# Microocontroller.net
KiCad netlist of a schematic drawn in Altium Designer
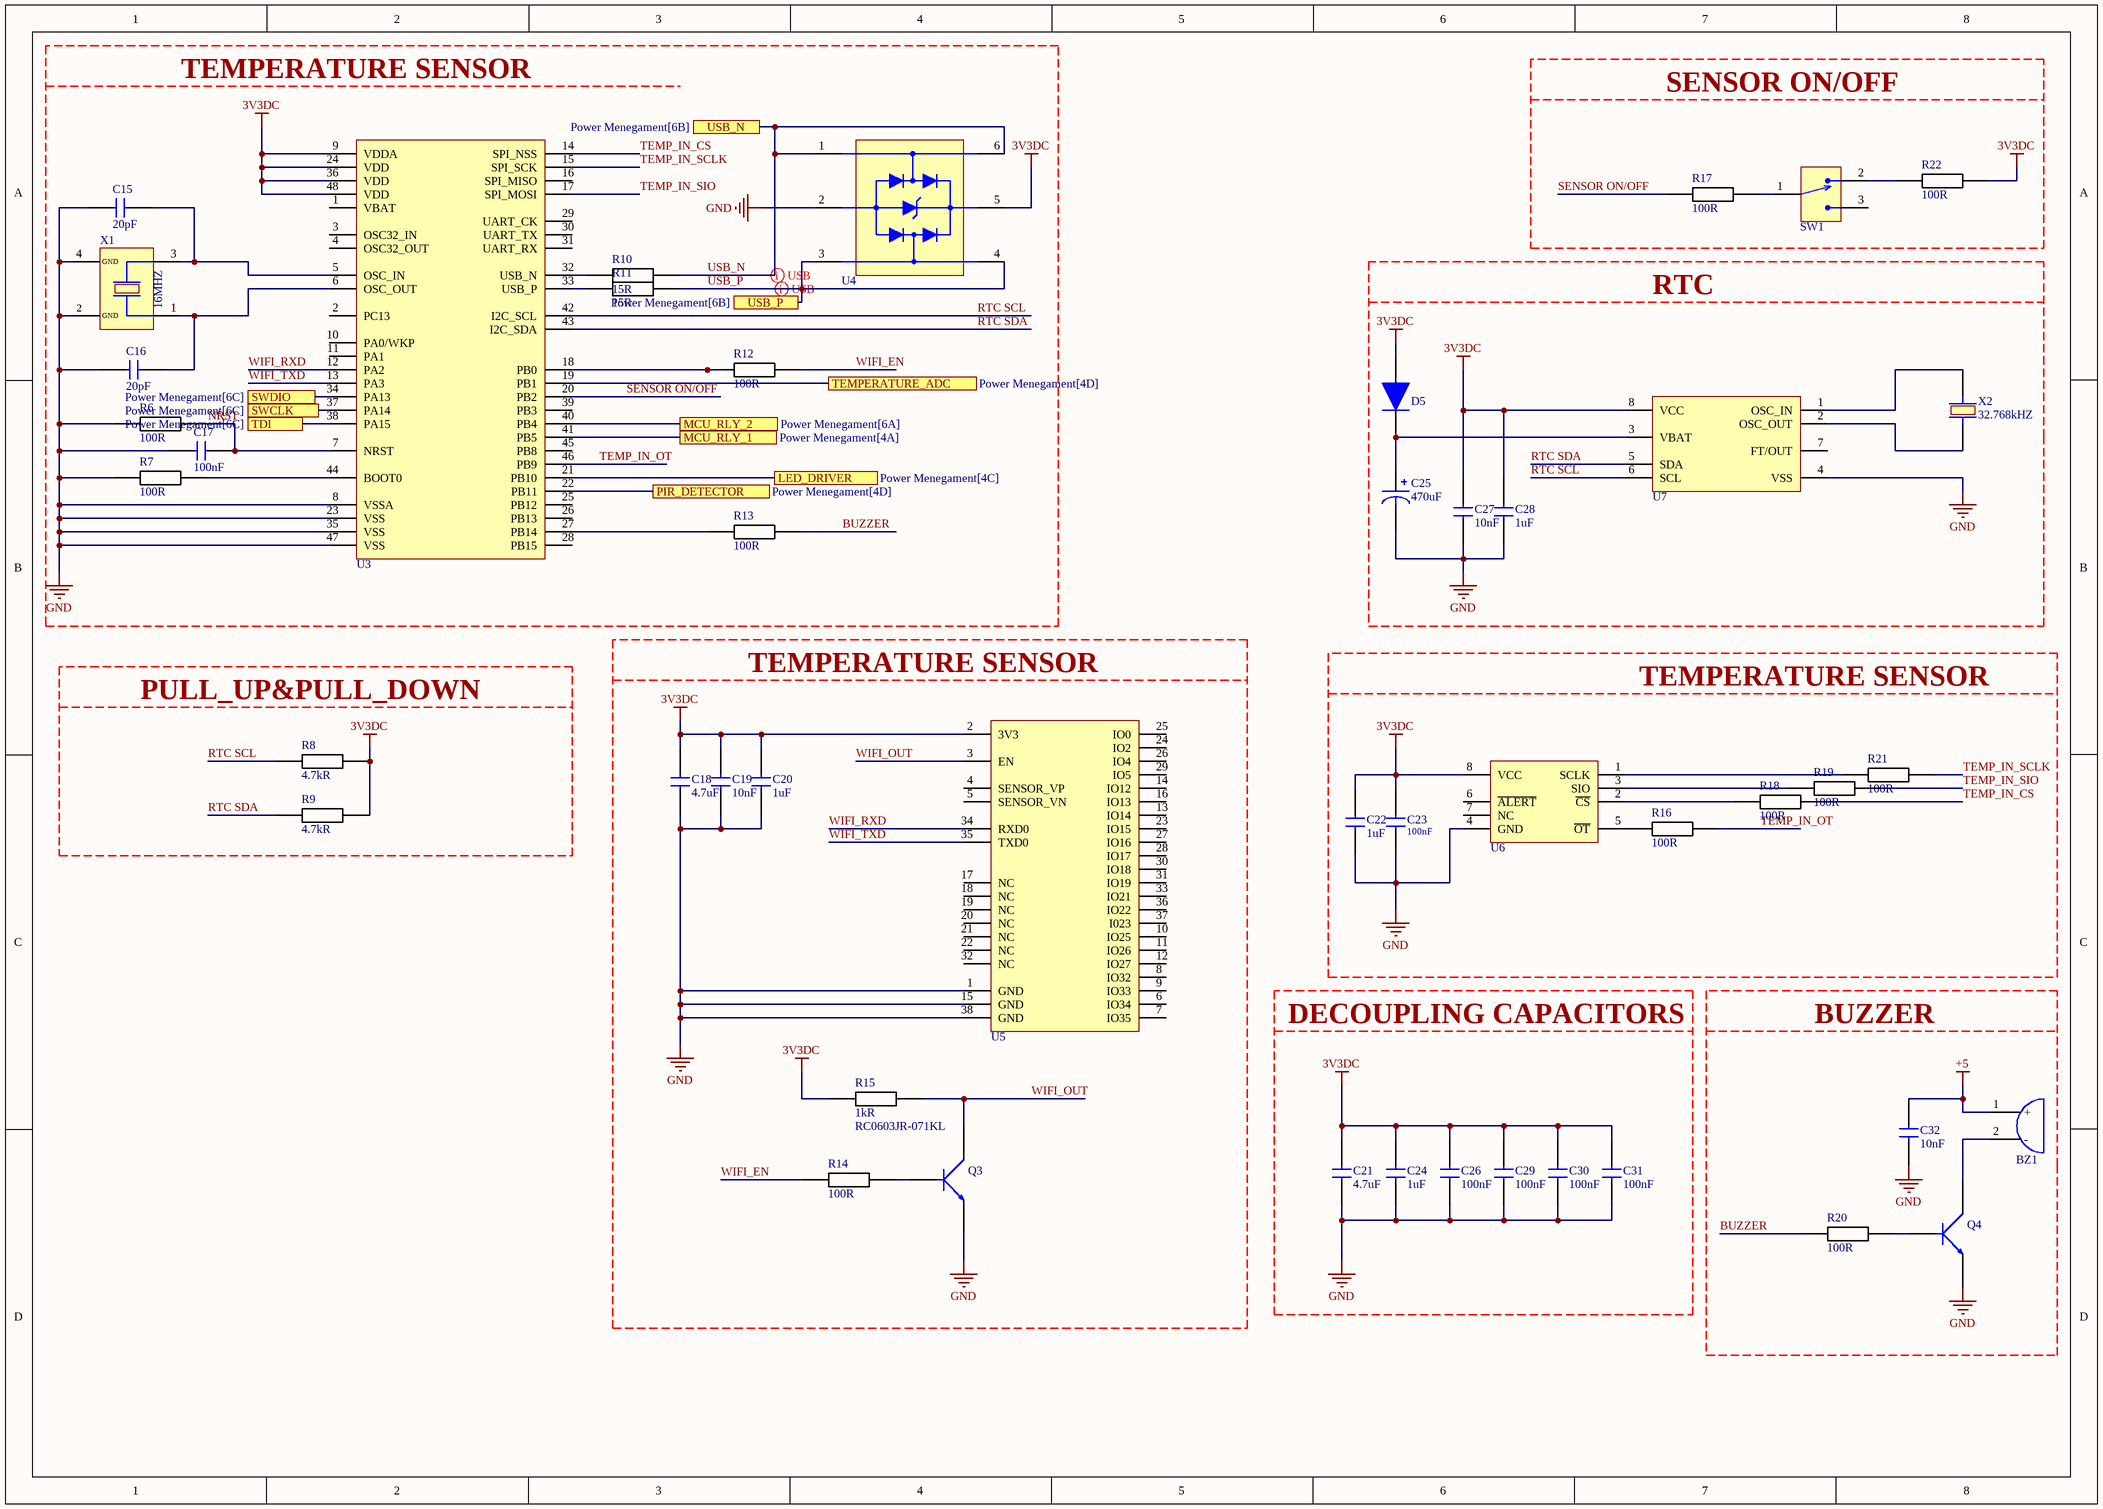
[diagram p0: Microocontroller.SchDoc]

(export (version "E")
  (design (tool "Eeschema 10.0.6"))
  (components
    (comp (ref "BZ1")
      (value "CMI-9605IC-0580T")
      (footprint "CMI-9605IC")
      (description "Buzzers Indicator, Internally Driven Magnetic 5 V 30mA 2.7kHz 80dB @ 5V, 10cm Through Hole PC Pins")
      (fields (field (name "MANUFACTURER") "CUI Devices") (field (name "DESIGNED BY") "Kerem"))
      (libsource (lib "library") (part "CMI-9605IC-0580T"))
    )
    (comp (ref "C15")
      (value "20pF")
      (footprint "CAP_0603")
      (description "Ceramic Capacitor, 50V, 0.00002uF, Surface Mount, 0603")
      (fields
        (field (name "MANUFACTURER") "Samsung")
        (field (name "MANUFACTURER PART NUMBER") "CL10C200JB8NNNC")
        (field (name "DESIGNED BY") "Kerem")
      )
      (libsource (lib "library") (part "CAP_CER_20pF_0603"))
    )
    (comp (ref "C16")
      (value "20pF")
      (footprint "CAP_0603")
      (description "Ceramic Capacitor, 50V, 0.00002uF, Surface Mount, 0603")
      (fields
        (field (name "MANUFACTURER") "Samsung")
        (field (name "MANUFACTURER PART NUMBER") "CL10C200JB8NNNC")
        (field (name "DESIGNED BY") "Kerem")
      )
      (libsource (lib "library") (part "CAP_CER_20pF_0603"))
    )
    (comp (ref "C17")
      (value "100nF")
      (footprint "CAP_0805")
      (description "Ceramic Capacitor,50V, %10, 0.1uF, Surface Mount, 0805")
      (fields
        (field (name "MANUFACTURER") "Samsung")
        (field (name "MANUFACTURER PART NUMBER") "CL21B104KBCNNNC")
        (field (name "DESIGNED BY") "Kerem")
      )
      (libsource (lib "library") (part "CAP_CER_100nF_0805"))
    )
    (comp (ref "C18")
      (value "4.7uF")
      (footprint "CAP_0805")
      (description "CAP CER 4.7uF,%10, Surface Mount, 0805")
      (fields
        (field (name "MANUFACTURER") "Samsung")
        (field (name "MANUFACTURER PART NUMBER") "CL21A475KAQNNNE")
        (field (name "DESIGNED BY") "Kerem")
      )
      (libsource (lib "library") (part "CAP_CER_4.7uF_0805"))
    )
    (comp (ref "C19")
      (value "10nF")
      (footprint "CAP_0603")
      (description "Ceramic Capacitor,16V, 10%, 0.01uF, Surface Mount, 0603")
      (fields
        (field (name "MANUFACTURER") "Walsin Technologies")
        (field (name "MANUFACTURER PART NUMBER") "0603B103K160CT")
        (field (name "DESIGNED BY") "Kerem")
      )
      (libsource (lib "library") (part "CAP_CER_10nF_0603"))
    )
    (comp (ref "C20")
      (value "1uF")
      (footprint "CAP_0805")
      (description "Cap CER, 1uF, 16V, 0805;")
      (fields
        (field (name "MANUFACTURER") "KEMET")
        (field (name "MANUFACTURER PART NUMBER") "CHA08C105K4RXL7189")
        (field (name "DESIGNED BY") "Kerem")
      )
      (libsource (lib "library") (part "CAP_CER_1uF_0805"))
    )
    (comp (ref "C21")
      (value "4.7uF")
      (footprint "CAP_0805")
      (description "CAP CER 4.7uF,%10, Surface Mount, 0805")
      (fields
        (field (name "MANUFACTURER") "Samsung")
        (field (name "MANUFACTURER PART NUMBER") "CL21A475KAQNNNE")
        (field (name "DESIGNED BY") "Kerem")
      )
      (libsource (lib "library") (part "CAP_CER_4.7uF_0805"))
    )
    (comp (ref "C22")
      (value "1uF")
      (footprint "CAP_0805")
      (description "Cap CER, 1uF, 16V, 0805;")
      (fields
        (field (name "MANUFACTURER") "KEMET")
        (field (name "MANUFACTURER PART NUMBER") "CHA08C105K4RXL7189")
        (field (name "DESIGNED BY") "Kerem")
      )
      (libsource (lib "library") (part "CAP_CER_1uF_0805"))
    )
    (comp (ref "C23")
      (value "100nF")
      (footprint "CAP_0603")
      (description "0.1 µF ±20% 50V Ceramic Capacitor X7R 0603 (1608 Metric)")
      (fields
        (field (name "MANUFACTURER") "KEMET")
        (field (name "MANUFACTURER PART NUMBER") "C0603C104M5RACTU")
      )
      (libsource (lib "library") (part "CAP CER 100nF 0603"))
    )
    (comp (ref "C24")
      (value "1uF")
      (footprint "CAP_0805")
      (description "Cap CER, 1uF, 16V, 0805;")
      (fields
        (field (name "MANUFACTURER") "KEMET")
        (field (name "MANUFACTURER PART NUMBER") "CHA08C105K4RXL7189")
        (field (name "DESIGNED BY") "Kerem")
      )
      (libsource (lib "library") (part "CAP_CER_1uF_0805"))
    )
    (comp (ref "C25")
      (value "470uF")
      (footprint "CAP_RADİAL_D10_R5")
      (fields
        (field (name "MANUFACTURER") "KEMET")
        (field (name "MANUFACTURER PART NUMBER") "ESH477M035AH4AA")
        (field (name "DESIGNED BY") "Kerem")
      )
      (libsource (lib "library") (part "CAP_ALU_470uF"))
    )
    (comp (ref "C26")
      (value "100nF")
      (footprint "CAP_0805")
      (description "Ceramic Capacitor,50V, %10, 0.1uF, Surface Mount, 0805")
      (fields
        (field (name "MANUFACTURER") "Samsung")
        (field (name "MANUFACTURER PART NUMBER") "CL21B104KBCNNNC")
        (field (name "DESIGNED BY") "Kerem")
      )
      (libsource (lib "library") (part "CAP_CER_100nF_0805"))
    )
    (comp (ref "C27")
      (value "10nF")
      (footprint "CAP_0603")
      (description "Ceramic Capacitor,16V, 10%, 0.01uF, Surface Mount, 0603")
      (fields
        (field (name "MANUFACTURER") "Walsin Technologies")
        (field (name "MANUFACTURER PART NUMBER") "0603B103K160CT")
        (field (name "DESIGNED BY") "Kerem")
      )
      (libsource (lib "library") (part "CAP_CER_10nF_0603"))
    )
    (comp (ref "C28")
      (value "1uF")
      (footprint "CAP_0805")
      (description "Cap CER, 1uF, 16V, 0805;")
      (fields
        (field (name "MANUFACTURER") "KEMET")
        (field (name "MANUFACTURER PART NUMBER") "CHA08C105K4RXL7189")
        (field (name "DESIGNED BY") "Kerem")
      )
      (libsource (lib "library") (part "CAP_CER_1uF_0805"))
    )
    (comp (ref "C29")
      (value "100nF")
      (footprint "CAP_0805")
      (description "Ceramic Capacitor,50V, %10, 0.1uF, Surface Mount, 0805")
      (fields
        (field (name "MANUFACTURER") "Samsung")
        (field (name "MANUFACTURER PART NUMBER") "CL21B104KBCNNNC")
        (field (name "DESIGNED BY") "Kerem")
      )
      (libsource (lib "library") (part "CAP_CER_100nF_0805"))
    )
    (comp (ref "C30")
      (value "100nF")
      (footprint "CAP_0805")
      (description "Ceramic Capacitor,50V, %10, 0.1uF, Surface Mount, 0805")
      (fields
        (field (name "MANUFACTURER") "Samsung")
        (field (name "MANUFACTURER PART NUMBER") "CL21B104KBCNNNC")
        (field (name "DESIGNED BY") "Kerem")
      )
      (libsource (lib "library") (part "CAP_CER_100nF_0805"))
    )
    (comp (ref "C31")
      (value "100nF")
      (footprint "CAP_0805")
      (description "Ceramic Capacitor,50V, %10, 0.1uF, Surface Mount, 0805")
      (fields
        (field (name "MANUFACTURER") "Samsung")
        (field (name "MANUFACTURER PART NUMBER") "CL21B104KBCNNNC")
        (field (name "DESIGNED BY") "Kerem")
      )
      (libsource (lib "library") (part "CAP_CER_100nF_0805"))
    )
    (comp (ref "C32")
      (value "10nF")
      (footprint "CAP_0603")
      (description "Ceramic Capacitor,16V, 10%, 0.01uF, Surface Mount, 0603")
      (fields
        (field (name "MANUFACTURER") "Walsin Technologies")
        (field (name "MANUFACTURER PART NUMBER") "0603B103K160CT")
        (field (name "DESIGNED BY") "Kerem")
      )
      (libsource (lib "library") (part "CAP_CER_10nF_0603"))
    )
    (comp (ref "D5")
      (value "1N4148WS")
      (footprint "SOD323F")
      (description "Rectifier Diode, 1 Phase, 1 Element, 0.15A, 100V V(RRM), Silicon")
      (fields
        (field (name "MANUFACTURER") "ON Semiconductor / Fairchild")
        (field (name "DESIGNED BY") "Kerem")
      )
      (libsource (lib "library") (part "1N4148WS"))
    )
    (comp (ref "Q3")
      (value "MMBT3904-7-F")
      (footprint "SOT-23F")
      (description "Small Signal Bipolar Transistor, 0.2A I(C), 40V V(BR)CEO, 1-Element, NPN, Silicon")
      (fields (field (name "MANUFACTURER") "Diodes Zetex") (field (name "DESIGNED BY") "Kerem"))
      (libsource (lib "library") (part "MMBT3904-7-F"))
    )
    (comp (ref "Q4")
      (value "MMBT3904-7-F")
      (footprint "SOT-23F")
      (description "Small Signal Bipolar Transistor, 0.2A I(C), 40V V(BR)CEO, 1-Element, NPN, Silicon")
      (fields (field (name "MANUFACTURER") "Diodes Zetex") (field (name "DESIGNED BY") "Kerem"))
      (libsource (lib "library") (part "MMBT3904-7-F"))
    )
    (comp (ref "R6")
      (value "100R")
      (footprint "RES_0603")
      (description "0.1W, 100ohm, 75V, 1% Surface Mount, 0603")
      (fields
        (field (name "MANUFACTURER") "Yageo")
        (field (name "MANUFACTURER PART NUMBER") "RC0603FR-07100RL")
        (field (name "DESIGNED BY") "Kerem")
      )
      (libsource (lib "library") (part "RES_100 OHM_0603"))
    )
    (comp (ref "R7")
      (value "100R")
      (footprint "RES_0603")
      (description "0.1W, 100ohm, 75V, 1% Surface Mount, 0603")
      (fields
        (field (name "MANUFACTURER") "Yageo")
        (field (name "MANUFACTURER PART NUMBER") "RC0603FR-07100RL")
        (field (name "DESIGNED BY") "Kerem")
      )
      (libsource (lib "library") (part "RES_100 OHM_0603"))
    )
    (comp (ref "R8")
      (value "4.7kR")
      (footprint "RES_0603")
      (description "0.1W, 4700ohm, 75V, 5% Surface Mount, 0603")
      (fields
        (field (name "MANUFACTURER") "Yageo")
        (field (name "MANUFACTURER PART NUMBER") "RC0603JR-074K7L")
        (field (name "DESIGNED BY") "Kerem")
      )
      (libsource (lib "library") (part "RES_4K7 OHM_0603"))
    )
    (comp (ref "R9")
      (value "4.7kR")
      (footprint "RES_0603")
      (description "0.1W, 4700ohm, 75V, 5% Surface Mount, 0603")
      (fields
        (field (name "MANUFACTURER") "Yageo")
        (field (name "MANUFACTURER PART NUMBER") "RC0603JR-074K7L")
        (field (name "DESIGNED BY") "Kerem")
      )
      (libsource (lib "library") (part "RES_4K7 OHM_0603"))
    )
    (comp (ref "R10")
      (value "15R")
      (footprint "RES_0603")
      (description "Fixed Resistor, 0.1W, 15ohm, 75V, 5% Surface Mount, 0603")
      (fields
        (field (name "MANUFACTURER") "Yageo")
        (field (name "MANUFACTURER PART NUMBER") "RC0603JR-0715RL")
        (field (name "DESIGNED BY") "Kerem")
      )
      (libsource (lib "library") (part "RES_15 OHM_0603"))
    )
    (comp (ref "R11")
      (value "15R")
      (footprint "RES_0603")
      (description "Fixed Resistor, 0.1W, 15ohm, 75V, 5% Surface Mount, 0603")
      (fields
        (field (name "MANUFACTURER") "Yageo")
        (field (name "MANUFACTURER PART NUMBER") "RC0603JR-0715RL")
        (field (name "DESIGNED BY") "Kerem")
      )
      (libsource (lib "library") (part "RES_15 OHM_0603"))
    )
    (comp (ref "R12")
      (value "100R")
      (footprint "RES_0603")
      (description "0.1W, 100ohm, 75V, 1% Surface Mount, 0603")
      (fields
        (field (name "MANUFACTURER") "Yageo")
        (field (name "MANUFACTURER PART NUMBER") "RC0603FR-07100RL")
        (field (name "DESIGNED BY") "Kerem")
      )
      (libsource (lib "library") (part "RES_100 OHM_0603"))
    )
    (comp (ref "R13")
      (value "100R")
      (footprint "RES_0603")
      (description "0.1W, 100ohm, 75V, 1% Surface Mount, 0603")
      (fields
        (field (name "MANUFACTURER") "Yageo")
        (field (name "MANUFACTURER PART NUMBER") "RC0603FR-07100RL")
        (field (name "DESIGNED BY") "Kerem")
      )
      (libsource (lib "library") (part "RES_100 OHM_0603"))
    )
    (comp (ref "R14")
      (value "100R")
      (footprint "RES_0603")
      (description "0.1W, 100ohm, 75V, 1% Surface Mount, 0603")
      (fields
        (field (name "MANUFACTURER") "Yageo")
        (field (name "MANUFACTURER PART NUMBER") "RC0603FR-07100RL")
        (field (name "DESIGNED BY") "Kerem")
      )
      (libsource (lib "library") (part "RES_100 OHM_0603"))
    )
    (comp (ref "R15")
      (value "RC0603JR-071KL")
      (footprint "RES_0603")
      (description "0.1W, 1000ohm, 75V, 5%, Surface Mount, 0603")
      (fields
        (field (name "MANUFACTURER") "Yageo")
        (field (name "TOLERANCE") "5%")
        (field (name "ALTIUM_VALUE") "1kR")
        (field (name "DESIGNED BY") "Kerem")
      )
      (libsource (lib "library") (part "RES_1K OHM_0603"))
    )
    (comp (ref "R16")
      (value "100R")
      (footprint "RES_0603")
      (description "0.1W, 100ohm, 75V, 1% Surface Mount, 0603")
      (fields
        (field (name "MANUFACTURER") "Yageo")
        (field (name "MANUFACTURER PART NUMBER") "RC0603FR-07100RL")
        (field (name "DESIGNED BY") "Kerem")
      )
      (libsource (lib "library") (part "RES_100 OHM_0603"))
    )
    (comp (ref "R17")
      (value "100R")
      (footprint "RES_0603")
      (description "0.1W, 100ohm, 75V, 1% Surface Mount, 0603")
      (fields
        (field (name "MANUFACTURER") "Yageo")
        (field (name "MANUFACTURER PART NUMBER") "RC0603FR-07100RL")
        (field (name "DESIGNED BY") "Kerem")
      )
      (libsource (lib "library") (part "RES_100 OHM_0603"))
    )
    (comp (ref "R18")
      (value "100R")
      (footprint "RES_0603")
      (description "0.1W, 100ohm, 75V, 1% Surface Mount, 0603")
      (fields
        (field (name "MANUFACTURER") "Yageo")
        (field (name "MANUFACTURER PART NUMBER") "RC0603FR-07100RL")
        (field (name "DESIGNED BY") "Kerem")
      )
      (libsource (lib "library") (part "RES_100 OHM_0603"))
    )
    (comp (ref "R19")
      (value "100R")
      (footprint "RES_0603")
      (description "0.1W, 100ohm, 75V, 1% Surface Mount, 0603")
      (fields
        (field (name "MANUFACTURER") "Yageo")
        (field (name "MANUFACTURER PART NUMBER") "RC0603FR-07100RL")
        (field (name "DESIGNED BY") "Kerem")
      )
      (libsource (lib "library") (part "RES_100 OHM_0603"))
    )
    (comp (ref "R20")
      (value "100R")
      (footprint "RES_0603")
      (description "0.1W, 100ohm, 75V, 1% Surface Mount, 0603")
      (fields
        (field (name "MANUFACTURER") "Yageo")
        (field (name "MANUFACTURER PART NUMBER") "RC0603FR-07100RL")
        (field (name "DESIGNED BY") "Kerem")
      )
      (libsource (lib "library") (part "RES_100 OHM_0603"))
    )
    (comp (ref "R21")
      (value "100R")
      (footprint "RES_0603")
      (description "0.1W, 100ohm, 75V, 1% Surface Mount, 0603")
      (fields
        (field (name "MANUFACTURER") "Yageo")
        (field (name "MANUFACTURER PART NUMBER") "RC0603FR-07100RL")
        (field (name "DESIGNED BY") "Kerem")
      )
      (libsource (lib "library") (part "RES_100 OHM_0603"))
    )
    (comp (ref "R22")
      (value "100R")
      (footprint "RES_0603")
      (description "0.1W, 100ohm, 75V, 1% Surface Mount, 0603")
      (fields
        (field (name "MANUFACTURER") "Yageo")
        (field (name "MANUFACTURER PART NUMBER") "RC0603FR-07100RL")
        (field (name "DESIGNED BY") "Kerem")
      )
      (libsource (lib "library") (part "RES_100 OHM_0603"))
    )
    (comp (ref "SW1")
      (value "EG1215AA")
      (footprint "EG1215AA")
      (description "Slide Switch")
      (fields (field (name "MANUFACTURER") "E-Switch") (field (name "DESIGNED BY") "Kerem"))
      (libsource (lib "library") (part "EG1215AA"))
    )
    (comp (ref "U3")
      (value "STM32F103C6T6A")
      (footprint "LQFP48")
      (description "RISC Microcontroller, 32-Bit, FLASH, CORTEX-M3 CPU, 72MHz, CMOS, PQFP48")
      (fields (field (name "MANUFACTURER") "STMicroelectronics") (field (name "DESIGNED BY") "Kerem"))
      (libsource (lib "library") (part "STM32F103C6T6A"))
    )
    (comp (ref "U4")
      (value "USBLC6-2SC6")
      (footprint "SOT-23-6L")
      (description "Trans Voltage Suppressor Diode, 5V V(RWM), Unidirectional, 1 Element, Silicon")
      (fields (field (name "MANUFACTURER") "STMicroelectronics") (field (name "DESIGNED BY") "Kerem"))
      (libsource (lib "library") (part "USB PROTECTION"))
    )
    (comp (ref "U5")
      (value "ESP32-WROOM-32E-4MB")
      (footprint "ESP32-32E")
      (description "SMD module, ESP32-D0WD-V3, ESP32 ECO V3, 4 MB SPI flash, PCB antenna")
      (fields
        (field (name "MANUFACTURER") "Espressif Systems")
        (field (name "MANUFACTURER PART NUMBER") "ESP32-WROOM-32E(M113EH3200PH3Q0)")
        (field (name "DESIGNED BY") "Kerem")
      )
      (libsource (lib "library") (part "ESP32-WROOM-32E-4MB"))
    )
    (comp (ref "U6")
      (value "MAX6662")
      (footprint "SOIC8")
      (description "Serial Switch/Digital Sensor, 12 Bit(s), 2.50Cel, BICMOS, Rectangular, 8 Pin, Surface Mount")
      (fields
        (field (name "MANUFACTURER") "Maxim")
        (field (name "MANUFACTURER PART NUMBER") "MAX6662MSA+")
        (field (name "DESIGNED BY") "Kerem")
      )
      (libsource (lib "library") (part "MAX6662"))
    )
    (comp (ref "U7")
      (value "M41T00SM6F")
      (footprint "SOIC8")
      (description "Real Time Clock, Volatile, 0 Timer(s), CMOS, PDSO8")
      (fields (field (name "MANUFACTURER") "STMicroelectronics") (field (name "DESIGNED BY") "Kerem"))
      (libsource (lib "library") (part "M41T00SM6F"))
    )
    (comp (ref "X1")
      (value "ECS-160-20-30B-TR")
      (footprint "ECS")
      (description "Parallel - Fundamental Quartz Crystal, 16MHz Nom")
      (fields
        (field (name "MANUFACTURER") "ECS International")
        (field (name "CRYSTAL_VALUE") "16MHZ")
        (field (name "DESIGNED BY") "Kerem")
      )
      (libsource (lib "library") (part "CRYSTLA_16MHZ"))
    )
    (comp (ref "X2")
      (value "ABS05-32.768KHZ-T")
      (footprint "ABS05")
      (description "Parallel - Fundamental Quartz Crystal, 0.032768MHz Nom")
      (fields
        (field (name "MANUFACTURER") "Abracon")
        (field (name "CRYSTAL_VALUE") "32.768kHZ")
        (field (name "DESIGNED BY") "Kerem")
      )
      (libsource (lib "library") (part "CRYSTAL_32768kHZ"))
    )
  )
  (nets
    (net (code "1") (name "+5") (class "Default")
      (node (ref "BZ1") (pin "1") (pinfunction "+_1") (pintype "passive"))
      (node (ref "C32") (pin "2") (pinfunction "2_2") (pintype "passive"))
    )
    (net (code "2") (name "/BUZZER") (class "Default")
      (node (ref "R13") (pin "2") (pinfunction "2_2") (pintype "passive"))
      (node (ref "R20") (pin "1") (pinfunction "1_1") (pintype "passive"))
    )
    (net (code "3") (name "/LED_DRIVER") (class "Default")
      (node (ref "U3") (pin "21") (pinfunction "PB10_21") (pintype "passive"))
    )
    (net (code "4") (name "/MCU_RLY_1") (class "Default")
      (node (ref "U3") (pin "41") (pinfunction "PB5_41") (pintype "passive"))
    )
    (net (code "5") (name "/MCU_RLY_2") (class "Default")
      (node (ref "U3") (pin "40") (pinfunction "PB4_40") (pintype "passive"))
    )
    (net (code "6") (name "/NRST") (class "Default")
      (node (ref "C17") (pin "1") (pinfunction "1_1") (pintype "passive"))
      (node (ref "R6") (pin "2") (pinfunction "2_2") (pintype "passive"))
      (node (ref "U3") (pin "7") (pinfunction "NRST_7") (pintype "passive"))
    )
    (net (code "7") (name "/PIR_DETECTOR") (class "Default")
      (node (ref "U3") (pin "22") (pinfunction "PB11_22") (pintype "passive"))
    )
    (net (code "8") (name "/RTC SCL") (class "Default")
      (node (ref "R8") (pin "1") (pinfunction "1_1") (pintype "passive"))
      (node (ref "U3") (pin "42") (pinfunction "I2C_SCL_42") (pintype "passive"))
      (node (ref "U7") (pin "6") (pinfunction "SCL_6") (pintype "passive"))
    )
    (net (code "9") (name "/RTC SDA") (class "Default")
      (node (ref "R9") (pin "1") (pinfunction "1_1") (pintype "passive"))
      (node (ref "U3") (pin "43") (pinfunction "I2C_SDA_43") (pintype "passive"))
      (node (ref "U7") (pin "5") (pinfunction "SDA_5") (pintype "passive"))
    )
    (net (code "10") (name "/SENSOR ON{slash}OFF") (class "Default")
      (node (ref "R17") (pin "1") (pinfunction "1_1") (pintype "passive"))
      (node (ref "U3") (pin "20") (pinfunction "PB2_20") (pintype "passive"))
    )
    (net (code "11") (name "/SWCLK") (class "Default")
      (node (ref "U3") (pin "37") (pinfunction "PA14_37") (pintype "passive"))
    )
    (net (code "12") (name "/SWDIO") (class "Default")
      (node (ref "U3") (pin "34") (pinfunction "PA13_34") (pintype "passive"))
    )
    (net (code "13") (name "/TDI") (class "Default")
      (node (ref "U3") (pin "38") (pinfunction "PA15_38") (pintype "passive"))
    )
    (net (code "14") (name "/TEMPERATURE_ADC") (class "Default")
      (node (ref "U3") (pin "19") (pinfunction "PB1_19") (pintype "passive"))
    )
    (net (code "15") (name "/TEMP_IN_CS") (class "Default")
      (node (ref "R18") (pin "2") (pinfunction "2_2") (pintype "passive"))
      (node (ref "U3") (pin "14") (pinfunction "SPI_NSS_14") (pintype "passive"))
    )
    (net (code "16") (name "/TEMP_IN_OT") (class "Default")
      (node (ref "R16") (pin "2") (pinfunction "2_2") (pintype "passive"))
      (node (ref "U3") (pin "46") (pinfunction "PB9_46") (pintype "passive"))
    )
    (net (code "17") (name "/TEMP_IN_SCLK") (class "Default")
      (node (ref "R21") (pin "2") (pinfunction "2_2") (pintype "passive"))
      (node (ref "U3") (pin "15") (pinfunction "SPI_SCK_15") (pintype "passive"))
    )
    (net (code "18") (name "/TEMP_IN_SIO") (class "Default")
      (node (ref "R19") (pin "2") (pinfunction "2_2") (pintype "passive"))
      (node (ref "U3") (pin "17") (pinfunction "SPI_MOSI_17") (pintype "passive"))
    )
    (net (code "19") (name "/USB_N") (class "Default")
      (node (ref "R10") (pin "2") (pinfunction "2_2") (pintype "passive"))
      (node (ref "U4") (pin "1") (pinfunction "1_1") (pintype "passive"))
      (node (ref "U4") (pin "6") (pinfunction "6_6") (pintype "passive"))
    )
    (net (code "20") (name "/USB_P") (class "Default")
      (node (ref "R11") (pin "2") (pinfunction "2_2") (pintype "passive"))
      (node (ref "U4") (pin "3") (pinfunction "3_3") (pintype "passive"))
      (node (ref "U4") (pin "4") (pinfunction "4_4") (pintype "passive"))
    )
    (net (code "21") (name "/WIFI_EN") (class "Default")
      (node (ref "R12") (pin "2") (pinfunction "2_2") (pintype "passive"))
      (node (ref "R14") (pin "1") (pinfunction "1_1") (pintype "passive"))
    )
    (net (code "22") (name "/WIFI_OUT") (class "Default")
      (node (ref "Q3") (pin "3") (pinfunction "C_3") (pintype "passive"))
      (node (ref "R15") (pin "2") (pinfunction "2_2") (pintype "passive"))
      (node (ref "U5") (pin "3") (pinfunction "EN_3") (pintype "passive"))
    )
    (net (code "23") (name "/WIFI_RXD") (class "Default")
      (node (ref "U3") (pin "12") (pinfunction "PA2_12") (pintype "passive"))
      (node (ref "U5") (pin "34") (pinfunction "RXD0_34") (pintype "passive"))
    )
    (net (code "24") (name "/WIFI_TXD") (class "Default")
      (node (ref "U3") (pin "13") (pinfunction "PA3_13") (pintype "passive"))
      (node (ref "U5") (pin "35") (pinfunction "TXD0_35") (pintype "passive"))
    )
    (net (code "25") (name "3V3DC") (class "Default")
      (node (ref "C18") (pin "2") (pinfunction "2_2") (pintype "passive"))
      (node (ref "C19") (pin "2") (pinfunction "2_2") (pintype "passive"))
      (node (ref "C20") (pin "2") (pinfunction "2_2") (pintype "passive"))
      (node (ref "C21") (pin "2") (pinfunction "2_2") (pintype "passive"))
      (node (ref "C22") (pin "2") (pinfunction "2_2") (pintype "passive"))
      (node (ref "C23") (pin "2") (pinfunction "2_2") (pintype "passive"))
      (node (ref "C24") (pin "2") (pinfunction "2_2") (pintype "passive"))
      (node (ref "C26") (pin "2") (pinfunction "2_2") (pintype "passive"))
      (node (ref "C27") (pin "2") (pinfunction "2_2") (pintype "passive"))
      (node (ref "C28") (pin "2") (pinfunction "2_2") (pintype "passive"))
      (node (ref "C29") (pin "2") (pinfunction "2_2") (pintype "passive"))
      (node (ref "C30") (pin "2") (pinfunction "2_2") (pintype "passive"))
      (node (ref "C31") (pin "2") (pinfunction "2_2") (pintype "passive"))
      (node (ref "D5") (pin "2") (pinfunction "2_2") (pintype "passive"))
      (node (ref "R15") (pin "1") (pinfunction "1_1") (pintype "passive"))
      (node (ref "R22") (pin "2") (pinfunction "2_2") (pintype "passive"))
      (node (ref "R8") (pin "2") (pinfunction "2_2") (pintype "passive"))
      (node (ref "R9") (pin "2") (pinfunction "2_2") (pintype "passive"))
      (node (ref "U3") (pin "24") (pinfunction "VDD_24") (pintype "passive"))
      (node (ref "U3") (pin "36") (pinfunction "VDD_36") (pintype "passive"))
      (node (ref "U3") (pin "48") (pinfunction "VDD_48") (pintype "passive"))
      (node (ref "U3") (pin "9") (pinfunction "VDDA_9") (pintype "passive"))
      (node (ref "U4") (pin "5") (pinfunction "5_5") (pintype "passive"))
      (node (ref "U5") (pin "2") (pinfunction "3V3_2") (pintype "passive"))
      (node (ref "U6") (pin "8") (pinfunction "VCC_8") (pintype "passive"))
      (node (ref "U7") (pin "8") (pinfunction "VCC_8") (pintype "passive"))
    )
    (net (code "26") (name "GND") (class "Default")
      (node (ref "C15") (pin "2") (pinfunction "2_2") (pintype "passive"))
      (node (ref "C16") (pin "1") (pinfunction "1_1") (pintype "passive"))
      (node (ref "C17") (pin "2") (pinfunction "2_2") (pintype "passive"))
      (node (ref "C18") (pin "1") (pinfunction "1_1") (pintype "passive"))
      (node (ref "C19") (pin "1") (pinfunction "1_1") (pintype "passive"))
      (node (ref "C20") (pin "1") (pinfunction "1_1") (pintype "passive"))
      (node (ref "C21") (pin "1") (pinfunction "1_1") (pintype "passive"))
      (node (ref "C22") (pin "1") (pinfunction "1_1") (pintype "passive"))
      (node (ref "C23") (pin "1") (pinfunction "1_1") (pintype "passive"))
      (node (ref "C24") (pin "1") (pinfunction "1_1") (pintype "passive"))
      (node (ref "C25") (pin "2") (pinfunction "2_2") (pintype "passive"))
      (node (ref "C26") (pin "1") (pinfunction "1_1") (pintype "passive"))
      (node (ref "C27") (pin "1") (pinfunction "1_1") (pintype "passive"))
      (node (ref "C28") (pin "1") (pinfunction "1_1") (pintype "passive"))
      (node (ref "C29") (pin "1") (pinfunction "1_1") (pintype "passive"))
      (node (ref "C30") (pin "1") (pinfunction "1_1") (pintype "passive"))
      (node (ref "C31") (pin "1") (pinfunction "1_1") (pintype "passive"))
      (node (ref "C32") (pin "1") (pinfunction "1_1") (pintype "passive"))
      (node (ref "Q3") (pin "2") (pinfunction "E_2") (pintype "passive"))
      (node (ref "Q4") (pin "2") (pinfunction "E_2") (pintype "passive"))
      (node (ref "R6") (pin "1") (pinfunction "1_1") (pintype "passive"))
      (node (ref "R7") (pin "1") (pinfunction "1_1") (pintype "passive"))
      (node (ref "U3") (pin "23") (pinfunction "VSS_23") (pintype "passive"))
      (node (ref "U3") (pin "35") (pinfunction "VSS_35") (pintype "passive"))
      (node (ref "U3") (pin "47") (pinfunction "VSS_47") (pintype "passive"))
      (node (ref "U3") (pin "8") (pinfunction "VSSA_8") (pintype "passive"))
      (node (ref "U4") (pin "2") (pinfunction "2_2") (pintype "passive"))
      (node (ref "U5") (pin "1") (pinfunction "GND_1") (pintype "passive"))
      (node (ref "U5") (pin "15") (pinfunction "GND_15") (pintype "passive"))
      (node (ref "U5") (pin "38") (pinfunction "GND_38") (pintype "passive"))
      (node (ref "U6") (pin "4") (pinfunction "GND_4") (pintype "passive"))
      (node (ref "U7") (pin "4") (pinfunction "VSS_4") (pintype "passive"))
      (node (ref "X1") (pin "2") (pinfunction "GND_2") (pintype "passive"))
      (node (ref "X1") (pin "4") (pinfunction "GND_4") (pintype "passive"))
    )
    (net (code "27") (name "Net-(BZ1--)") (class "Default")
      (node (ref "BZ1") (pin "2") (pinfunction "-_2") (pintype "passive"))
      (node (ref "Q4") (pin "3") (pinfunction "C_3") (pintype "passive"))
    )
    (net (code "28") (name "Net-(Q3-B)") (class "Default")
      (node (ref "Q3") (pin "1") (pinfunction "B_1") (pintype "passive"))
      (node (ref "R14") (pin "2") (pinfunction "2_2") (pintype "passive"))
    )
    (net (code "29") (name "Net-(Q4-B)") (class "Default")
      (node (ref "Q4") (pin "1") (pinfunction "B_1") (pintype "passive"))
      (node (ref "R20") (pin "2") (pinfunction "2_2") (pintype "passive"))
    )
    (net (code "30") (name "Net-(R17-Pad2)") (class "Default")
      (node (ref "R17") (pin "2") (pinfunction "2_2") (pintype "passive"))
      (node (ref "SW1") (pin "1") (pintype "passive"))
    )
    (net (code "31") (name "Net-(R22-Pad1)") (class "Default")
      (node (ref "R22") (pin "1") (pinfunction "1_1") (pintype "passive"))
      (node (ref "SW1") (pin "2") (pintype "passive"))
    )
    (net (code "32") (name "Net-(U3-BOOT0)") (class "Default")
      (node (ref "R7") (pin "2") (pinfunction "2_2") (pintype "passive"))
      (node (ref "U3") (pin "44") (pinfunction "BOOT0_44") (pintype "passive"))
    )
    (net (code "33") (name "Net-(U3-OSC_IN)") (class "Default")
      (node (ref "C15") (pin "1") (pinfunction "1_1") (pintype "passive"))
      (node (ref "U3") (pin "5") (pinfunction "OSC_IN_5") (pintype "passive"))
      (node (ref "X1") (pin "3") (pinfunction "3_3") (pintype "passive"))
    )
    (net (code "34") (name "Net-(U3-OSC_OUT)") (class "Default")
      (node (ref "C16") (pin "2") (pinfunction "2_2") (pintype "passive"))
      (node (ref "U3") (pin "6") (pinfunction "OSC_OUT_6") (pintype "passive"))
      (node (ref "X1") (pin "1") (pinfunction "1_1") (pintype "passive"))
    )
    (net (code "35") (name "Net-(U3-PB0)") (class "Default")
      (node (ref "R12") (pin "1") (pinfunction "1_1") (pintype "passive"))
      (node (ref "U3") (pin "18") (pinfunction "PB0_18") (pintype "passive"))
    )
    (net (code "36") (name "Net-(U3-PB14)") (class "Default")
      (node (ref "R13") (pin "1") (pinfunction "1_1") (pintype "passive"))
      (node (ref "U3") (pin "27") (pinfunction "PB14_27") (pintype "passive"))
    )
    (net (code "37") (name "Net-(U3-USB_N)") (class "Default")
      (node (ref "R10") (pin "1") (pinfunction "1_1") (pintype "passive"))
      (node (ref "U3") (pin "32") (pinfunction "USB_N_32") (pintype "passive"))
    )
    (net (code "38") (name "Net-(U3-USB_P)") (class "Default")
      (node (ref "R11") (pin "1") (pinfunction "1_1") (pintype "passive"))
      (node (ref "U3") (pin "33") (pinfunction "USB_P_33") (pintype "passive"))
    )
    (net (code "39") (name "Net-(U6-SCLK)") (class "Default")
      (node (ref "R21") (pin "1") (pinfunction "1_1") (pintype "passive"))
      (node (ref "U6") (pin "1") (pinfunction "SCLK_1") (pintype "passive"))
    )
    (net (code "40") (name "Net-(U6-SIO)") (class "Default")
      (node (ref "R19") (pin "1") (pinfunction "1_1") (pintype "passive"))
      (node (ref "U6") (pin "3") (pinfunction "SIO_3") (pintype "passive"))
    )
    (net (code "41") (name "Net-(U6-~{CS})") (class "Default")
      (node (ref "R18") (pin "1") (pinfunction "1_1") (pintype "passive"))
      (node (ref "U6") (pin "2") (pinfunction "~{CS}_2") (pintype "passive"))
    )
    (net (code "42") (name "Net-(U6-~{OT})") (class "Default")
      (node (ref "R16") (pin "1") (pinfunction "1_1") (pintype "passive"))
      (node (ref "U6") (pin "5") (pinfunction "~{OT}_5") (pintype "passive"))
    )
    (net (code "43") (name "Net-(U7-OSC_IN)") (class "Default")
      (node (ref "U7") (pin "1") (pinfunction "OSC_IN_1") (pintype "passive"))
      (node (ref "X2") (pin "2") (pinfunction "2_2") (pintype "passive"))
    )
    (net (code "44") (name "Net-(U7-OSC_OUT)") (class "Default")
      (node (ref "U7") (pin "2") (pinfunction "OSC_OUT_2") (pintype "passive"))
      (node (ref "X2") (pin "1") (pinfunction "1_1") (pintype "passive"))
    )
    (net (code "45") (name "Net-(U7-VBAT)") (class "Default")
      (node (ref "C25") (pin "1") (pinfunction "1_1") (pintype "passive"))
      (node (ref "D5") (pin "1") (pinfunction "1_1") (pintype "passive"))
      (node (ref "U7") (pin "3") (pinfunction "VBAT_3") (pintype "passive"))
    )
    (net (code "46") (name "unconnected-(SW1-Pad3)") (class "Default")
      (node (ref "SW1") (pin "3") (pintype "passive"))
    )
    (net (code "47") (name "unconnected-(U3-OSC32_IN-Pad3)") (class "Default")
      (node (ref "U3") (pin "3") (pinfunction "OSC32_IN_3") (pintype "passive"))
    )
    (net (code "48") (name "unconnected-(U3-OSC32_OUT-Pad4)") (class "Default")
      (node (ref "U3") (pin "4") (pinfunction "OSC32_OUT_4") (pintype "passive"))
    )
    (net (code "49") (name "unconnected-(U3-PA0{slash}WKP-Pad10)") (class "Default")
      (node (ref "U3") (pin "10") (pinfunction "PA0/WKP_10") (pintype "passive"))
    )
    (net (code "50") (name "unconnected-(U3-PA1-Pad11)") (class "Default")
      (node (ref "U3") (pin "11") (pinfunction "PA1_11") (pintype "passive"))
    )
    (net (code "51") (name "unconnected-(U3-PB3-Pad39)") (class "Default")
      (node (ref "U3") (pin "39") (pinfunction "PB3_39") (pintype "passive"))
    )
    (net (code "52") (name "unconnected-(U3-PB8-Pad45)") (class "Default")
      (node (ref "U3") (pin "45") (pinfunction "PB8_45") (pintype "passive"))
    )
    (net (code "53") (name "unconnected-(U3-PB12-Pad25)") (class "Default")
      (node (ref "U3") (pin "25") (pinfunction "PB12_25") (pintype "passive"))
    )
    (net (code "54") (name "unconnected-(U3-PB13-Pad26)") (class "Default")
      (node (ref "U3") (pin "26") (pinfunction "PB13_26") (pintype "passive"))
    )
    (net (code "55") (name "unconnected-(U3-PB15-Pad28)") (class "Default")
      (node (ref "U3") (pin "28") (pinfunction "PB15_28") (pintype "passive"))
    )
    (net (code "56") (name "unconnected-(U3-PC13-Pad2)") (class "Default")
      (node (ref "U3") (pin "2") (pinfunction "PC13_2") (pintype "passive"))
    )
    (net (code "57") (name "unconnected-(U3-SPI_MISO-Pad16)") (class "Default")
      (node (ref "U3") (pin "16") (pinfunction "SPI_MISO_16") (pintype "passive"))
    )
    (net (code "58") (name "unconnected-(U3-UART_CK-Pad29)") (class "Default")
      (node (ref "U3") (pin "29") (pinfunction "UART_CK_29") (pintype "passive"))
    )
    (net (code "59") (name "unconnected-(U3-UART_RX-Pad31)") (class "Default")
      (node (ref "U3") (pin "31") (pinfunction "UART_RX_31") (pintype "passive"))
    )
    (net (code "60") (name "unconnected-(U3-UART_TX-Pad30)") (class "Default")
      (node (ref "U3") (pin "30") (pinfunction "UART_TX_30") (pintype "passive"))
    )
    (net (code "61") (name "unconnected-(U3-VBAT-Pad1)") (class "Default")
      (node (ref "U3") (pin "1") (pinfunction "VBAT_1") (pintype "passive"))
    )
    (net (code "62") (name "unconnected-(U5-I023-Pad37)") (class "Default")
      (node (ref "U5") (pin "37") (pinfunction "I023_37") (pintype "passive"))
    )
    (net (code "63") (name "unconnected-(U5-IO0-Pad25)") (class "Default")
      (node (ref "U5") (pin "25") (pinfunction "IO0_25") (pintype "passive"))
    )
    (net (code "64") (name "unconnected-(U5-IO2-Pad24)") (class "Default")
      (node (ref "U5") (pin "24") (pinfunction "IO2_24") (pintype "passive"))
    )
    (net (code "65") (name "unconnected-(U5-IO4-Pad26)") (class "Default")
      (node (ref "U5") (pin "26") (pinfunction "IO4_26") (pintype "passive"))
    )
    (net (code "66") (name "unconnected-(U5-IO5-Pad29)") (class "Default")
      (node (ref "U5") (pin "29") (pinfunction "IO5_29") (pintype "passive"))
    )
    (net (code "67") (name "unconnected-(U5-IO12-Pad14)") (class "Default")
      (node (ref "U5") (pin "14") (pinfunction "IO12_14") (pintype "passive"))
    )
    (net (code "68") (name "unconnected-(U5-IO13-Pad16)") (class "Default")
      (node (ref "U5") (pin "16") (pinfunction "IO13_16") (pintype "passive"))
    )
    (net (code "69") (name "unconnected-(U5-IO14-Pad13)") (class "Default")
      (node (ref "U5") (pin "13") (pinfunction "IO14_13") (pintype "passive"))
    )
    (net (code "70") (name "unconnected-(U5-IO15-Pad23)") (class "Default")
      (node (ref "U5") (pin "23") (pinfunction "IO15_23") (pintype "passive"))
    )
    (net (code "71") (name "unconnected-(U5-IO16-Pad27)") (class "Default")
      (node (ref "U5") (pin "27") (pinfunction "IO16_27") (pintype "passive"))
    )
    (net (code "72") (name "unconnected-(U5-IO17-Pad28)") (class "Default")
      (node (ref "U5") (pin "28") (pinfunction "IO17_28") (pintype "passive"))
    )
    (net (code "73") (name "unconnected-(U5-IO18-Pad30)") (class "Default")
      (node (ref "U5") (pin "30") (pinfunction "IO18_30") (pintype "passive"))
    )
    (net (code "74") (name "unconnected-(U5-IO19-Pad31)") (class "Default")
      (node (ref "U5") (pin "31") (pinfunction "IO19_31") (pintype "passive"))
    )
    (net (code "75") (name "unconnected-(U5-IO21-Pad33)") (class "Default")
      (node (ref "U5") (pin "33") (pinfunction "IO21_33") (pintype "passive"))
    )
    (net (code "76") (name "unconnected-(U5-IO22-Pad36)") (class "Default")
      (node (ref "U5") (pin "36") (pinfunction "IO22_36") (pintype "passive"))
    )
    (net (code "77") (name "unconnected-(U5-IO25-Pad10)") (class "Default")
      (node (ref "U5") (pin "10") (pinfunction "IO25_10") (pintype "passive"))
    )
    (net (code "78") (name "unconnected-(U5-IO26-Pad11)") (class "Default")
      (node (ref "U5") (pin "11") (pinfunction "IO26_11") (pintype "passive"))
    )
    (net (code "79") (name "unconnected-(U5-IO27-Pad12)") (class "Default")
      (node (ref "U5") (pin "12") (pinfunction "IO27_12") (pintype "passive"))
    )
    (net (code "80") (name "unconnected-(U5-IO32-Pad8)") (class "Default")
      (node (ref "U5") (pin "8") (pinfunction "IO32_8") (pintype "passive"))
    )
    (net (code "81") (name "unconnected-(U5-IO33-Pad9)") (class "Default")
      (node (ref "U5") (pin "9") (pinfunction "IO33_9") (pintype "passive"))
    )
    (net (code "82") (name "unconnected-(U5-IO34-Pad6)") (class "Default")
      (node (ref "U5") (pin "6") (pinfunction "IO34_6") (pintype "passive"))
    )
    (net (code "83") (name "unconnected-(U5-IO35-Pad7)") (class "Default")
      (node (ref "U5") (pin "7") (pinfunction "IO35_7") (pintype "passive"))
    )
    (net (code "84") (name "unconnected-(U5-NC-Pad17)") (class "Default")
      (node (ref "U5") (pin "17") (pinfunction "NC_17") (pintype "passive"))
    )
    (net (code "85") (name "unconnected-(U5-NC-Pad18)") (class "Default")
      (node (ref "U5") (pin "18") (pinfunction "NC_18") (pintype "passive"))
    )
    (net (code "86") (name "unconnected-(U5-NC-Pad19)") (class "Default")
      (node (ref "U5") (pin "19") (pinfunction "NC_19") (pintype "passive"))
    )
    (net (code "87") (name "unconnected-(U5-NC-Pad20)") (class "Default")
      (node (ref "U5") (pin "20") (pinfunction "NC_20") (pintype "passive"))
    )
    (net (code "88") (name "unconnected-(U5-NC-Pad21)") (class "Default")
      (node (ref "U5") (pin "21") (pinfunction "NC_21") (pintype "passive"))
    )
    (net (code "89") (name "unconnected-(U5-NC-Pad22)") (class "Default")
      (node (ref "U5") (pin "22") (pinfunction "NC_22") (pintype "passive"))
    )
    (net (code "90") (name "unconnected-(U5-NC-Pad32)") (class "Default")
      (node (ref "U5") (pin "32") (pinfunction "NC_32") (pintype "passive"))
    )
    (net (code "91") (name "unconnected-(U5-SENSOR_VN-Pad5)") (class "Default")
      (node (ref "U5") (pin "5") (pinfunction "SENSOR_VN_5") (pintype "passive"))
    )
    (net (code "92") (name "unconnected-(U5-SENSOR_VP-Pad4)") (class "Default")
      (node (ref "U5") (pin "4") (pinfunction "SENSOR_VP_4") (pintype "passive"))
    )
    (net (code "93") (name "unconnected-(U6-NC-Pad7)") (class "Default")
      (node (ref "U6") (pin "7") (pinfunction "NC_7") (pintype "passive"))
    )
    (net (code "94") (name "unconnected-(U6-~{ALERT}-Pad6)") (class "Default")
      (node (ref "U6") (pin "6") (pinfunction "~{ALERT}_6") (pintype "passive"))
    )
    (net (code "95") (name "unconnected-(U7-FT{slash}OUT-Pad7)") (class "Default")
      (node (ref "U7") (pin "7") (pinfunction "FT/OUT_7") (pintype "passive"))
    )
  )
)
